# MainBord.net
KiCad netlist of a schematic drawn in Altium Designer
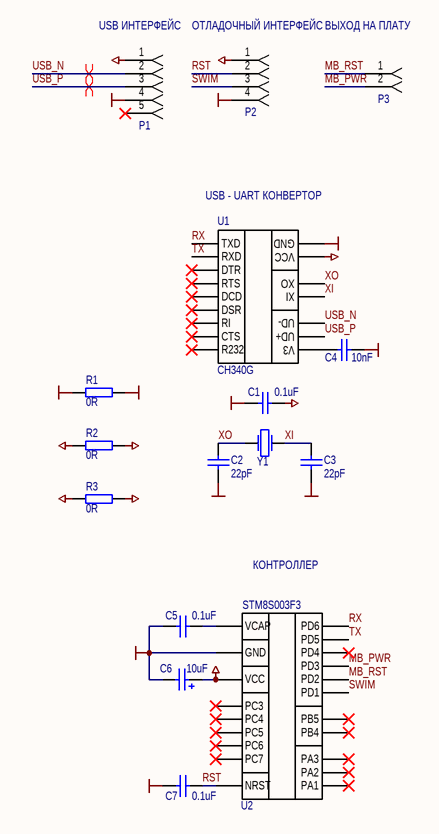
[diagram p0: MainBord.SchDoc]

(export (version "E")
  (design (tool "Eeschema 10.0.6"))
  (components
    (comp (ref "C1")
      (value "0.1uF")
      (footprint "Passive:CAP0603")
      (description "Surface mount ceramic capacitor")
      (fields (field (name "Comment") "CeramicCapacitor"))
      (libsource (lib "Passive") (part "CeramicCapacitor"))
    )
    (comp (ref "C2")
      (value "22pF")
      (footprint "Passive:CAP0402")
      (description "Surface mount ceramic capacitor")
      (fields (field (name "Comment") "CeramicCapacitor"))
      (libsource (lib "Passive") (part "CeramicCapacitor"))
    )
    (comp (ref "C3")
      (value "22pF")
      (footprint "Passive:CAP0402")
      (description "Surface mount ceramic capacitor")
      (fields (field (name "Comment") "CeramicCapacitor"))
      (libsource (lib "Passive") (part "CeramicCapacitor"))
    )
    (comp (ref "C4")
      (value "10nF")
      (footprint "Passive:CAP0603")
      (description "Surface mount ceramic capacitor")
      (fields (field (name "Comment") "CeramicCapacitor"))
      (libsource (lib "Passive") (part "CeramicCapacitor"))
    )
    (comp (ref "C5")
      (value "0.1uF")
      (footprint "Passive:CAP0603")
      (description "Surface mount ceramic capacitor")
      (fields (field (name "Comment") "CeramicCapacitor"))
      (libsource (lib "Passive") (part "CeramicCapacitor"))
    )
    (comp (ref "C6")
      (value "10uF")
      (footprint "Passive:CAP3216")
      (description "Surface mount tantalum capacitor")
      (fields (field (name "Comment") "TantalumCapacitor"))
      (libsource (lib "Passive") (part "TantalumCapacitor"))
    )
    (comp (ref "C7")
      (value "0.1uF")
      (footprint "Passive:CAP0603")
      (description "Surface mount ceramic capacitor")
      (fields (field (name "Comment") "CeramicCapacitor"))
      (libsource (lib "Passive") (part "CeramicCapacitor"))
    )
    (comp (ref "P1")
      (value "Disp")
      (footprint "Connectors:THT_MALE_1x5")
      (libsource (lib "Connectors") (part "XH2.54_5PIN"))
    )
    (comp (ref "P2")
      (value "Disp")
      (footprint "Connectors:653004114822")
      (libsource (lib "Connectors") (part "JST_XH_4PIN"))
    )
    (comp (ref "P3")
      (value "Disp")
      (footprint "Connectors:THT_MALE_1x2")
      (libsource (lib "Connectors") (part "XH2.54_2PIN"))
    )
    (comp (ref "R1")
      (value "0R")
      (footprint "Passive:RES0805_0_Ohm")
      (description "Surface mount resistor")
      (fields (field (name "Comment") "Resistor"))
      (libsource (lib "Passive") (part "Resistor"))
    )
    (comp (ref "R2")
      (value "0R")
      (footprint "Passive:RES0805_0_Ohm")
      (description "Surface mount resistor")
      (fields (field (name "Comment") "Resistor"))
      (libsource (lib "Passive") (part "Resistor"))
    )
    (comp (ref "R3")
      (value "0R")
      (footprint "Passive:RES0805_0_Ohm")
      (description "Surface mount resistor")
      (fields (field (name "Comment") "Resistor"))
      (libsource (lib "Passive") (part "Resistor"))
    )
    (comp (ref "U1")
      (value "CH340G")
      (footprint "IC:SOIC16_CH340G")
      (description "USB to UART Interface")
      (libsource (lib "IC") (part "CH340G"))
    )
    (comp (ref "U2")
      (value "STM8S003F3")
      (footprint "IC:TSOP65P640X120-20N")
      (libsource (lib "IC") (part "STM8S003F3"))
    )
    (comp (ref "Y1")
      (value "XTAL")
      (footprint "Misc:SMD3225")
      (description "Crystal Oscillator")
      (libsource (lib "Misc") (part "XTAL"))
    )
  )
  (nets
    (net (code "1") (name "/MB_PWR") (class "Default")
      (node (ref "P3") (pin "2") (pintype "passive"))
      (node (ref "U2") (pin "20") (pinfunction "PD3_20") (pintype "passive"))
    )
    (net (code "2") (name "/MB_RST") (class "Default")
      (node (ref "P3") (pin "1") (pintype "passive"))
      (node (ref "U2") (pin "19") (pinfunction "PD2_19") (pintype "passive"))
    )
    (net (code "3") (name "/RST") (class "Default")
      (node (ref "C7") (pin "2") (pinfunction "2_2") (pintype "passive"))
      (node (ref "P2") (pin "2") (pintype "passive"))
      (node (ref "U2") (pin "4") (pinfunction "NRST_4") (pintype "passive"))
    )
    (net (code "4") (name "/RX") (class "Default")
      (node (ref "U1") (pin "2") (pinfunction "TXD_2") (pintype "passive"))
      (node (ref "U2") (pin "3") (pinfunction "PD6_3") (pintype "passive"))
    )
    (net (code "5") (name "/SWIM") (class "Default")
      (node (ref "P2") (pin "3") (pintype "passive"))
      (node (ref "U2") (pin "18") (pinfunction "PD1_18") (pintype "passive"))
    )
    (net (code "6") (name "/TX") (class "Default")
      (node (ref "U1") (pin "3") (pinfunction "RXD_3") (pintype "passive"))
      (node (ref "U2") (pin "2") (pinfunction "PD5_2") (pintype "passive"))
    )
    (net (code "7") (name "/USB_N") (class "Default")
      (node (ref "P1") (pin "2") (pintype "passive"))
      (node (ref "U1") (pin "6") (pinfunction "UD-_6") (pintype "passive"))
    )
    (net (code "8") (name "/USB_P") (class "Default")
      (node (ref "P1") (pin "3") (pintype "passive"))
      (node (ref "U1") (pin "5") (pinfunction "UD+_5") (pintype "passive"))
    )
    (net (code "9") (name "/XI") (class "Default")
      (node (ref "C3") (pin "2") (pinfunction "2_2") (pintype "passive"))
      (node (ref "U1") (pin "7") (pinfunction "XI_7") (pintype "passive"))
      (node (ref "Y1") (pin "3") (pinfunction "Out_3") (pintype "passive"))
    )
    (net (code "10") (name "/XO") (class "Default")
      (node (ref "C2") (pin "2") (pinfunction "2_2") (pintype "passive"))
      (node (ref "U1") (pin "8") (pinfunction "XO_8") (pintype "passive"))
      (node (ref "Y1") (pin "1") (pinfunction "In_1") (pintype "passive"))
    )
    (net (code "11") (name "GND") (class "Default")
      (node (ref "C1") (pin "1") (pinfunction "1_1") (pintype "passive"))
      (node (ref "C2") (pin "1") (pinfunction "1_1") (pintype "passive"))
      (node (ref "C3") (pin "1") (pinfunction "1_1") (pintype "passive"))
      (node (ref "C4") (pin "1") (pinfunction "1_1") (pintype "passive"))
      (node (ref "C5") (pin "1") (pinfunction "1_1") (pintype "passive"))
      (node (ref "C6") (pin "1") (pinfunction "1_1") (pintype "passive"))
      (node (ref "C7") (pin "1") (pinfunction "1_1") (pintype "passive"))
      (node (ref "P1") (pin "4") (pintype "passive"))
      (node (ref "P2") (pin "4") (pintype "passive"))
      (node (ref "R1") (pin "1") (pinfunction "1_1") (pintype "passive"))
      (node (ref "R1") (pin "2") (pinfunction "2_2") (pintype "passive"))
      (node (ref "U1") (pin "1") (pinfunction "GND_1") (pintype "passive"))
      (node (ref "U2") (pin "7") (pinfunction "GND_7") (pintype "power_in"))
    )
    (net (code "12") (name "Net-(U1-V3)") (class "Default")
      (node (ref "C4") (pin "2") (pinfunction "2_2") (pintype "passive"))
      (node (ref "U1") (pin "4") (pinfunction "V3_4") (pintype "passive"))
    )
    (net (code "13") (name "Net-(U2-VCAP)") (class "Default")
      (node (ref "C5") (pin "2") (pinfunction "2_2") (pintype "passive"))
      (node (ref "U2") (pin "8") (pinfunction "VCAP_8") (pintype "power_in"))
    )
    (net (code "14") (name "VCC") (class "Default")
      (node (ref "C1") (pin "2") (pinfunction "2_2") (pintype "passive"))
      (node (ref "C6") (pin "2") (pinfunction "2_2") (pintype "passive"))
      (node (ref "P1") (pin "1") (pintype "passive"))
      (node (ref "P2") (pin "1") (pintype "passive"))
      (node (ref "R2") (pin "1") (pinfunction "1_1") (pintype "passive"))
      (node (ref "R2") (pin "2") (pinfunction "2_2") (pintype "passive"))
      (node (ref "R3") (pin "1") (pinfunction "1_1") (pintype "passive"))
      (node (ref "R3") (pin "2") (pinfunction "2_2") (pintype "passive"))
      (node (ref "U1") (pin "16") (pinfunction "VCC_16") (pintype "passive"))
      (node (ref "U2") (pin "9") (pinfunction "VCC_9") (pintype "power_in"))
    )
    (net (code "15") (name "unconnected-(P1-Pad5)") (class "Default")
      (node (ref "P1") (pin "5") (pintype "passive+no_connect"))
    )
    (net (code "16") (name "unconnected-(U1-R232-Pad15)") (class "Default")
      (node (ref "U1") (pin "15") (pinfunction "R232_15") (pintype "passive+no_connect"))
    )
    (net (code "17") (name "unconnected-(U1-~{CTS}-Pad9)") (class "Default")
      (node (ref "U1") (pin "9") (pinfunction "~{CTS}_9") (pintype "passive+no_connect"))
    )
    (net (code "18") (name "unconnected-(U1-~{DCD}-Pad12)") (class "Default")
      (node (ref "U1") (pin "12") (pinfunction "~{DCD}_12") (pintype "passive+no_connect"))
    )
    (net (code "19") (name "unconnected-(U1-~{DSR}-Pad10)") (class "Default")
      (node (ref "U1") (pin "10") (pinfunction "~{DSR}_10") (pintype "passive+no_connect"))
    )
    (net (code "20") (name "unconnected-(U1-~{DTR}-Pad13)") (class "Default")
      (node (ref "U1") (pin "13") (pinfunction "~{DTR}_13") (pintype "passive+no_connect"))
    )
    (net (code "21") (name "unconnected-(U1-~{RI}-Pad11)") (class "Default")
      (node (ref "U1") (pin "11") (pinfunction "~{RI}_11") (pintype "passive+no_connect"))
    )
    (net (code "22") (name "unconnected-(U1-~{RTS}-Pad14)") (class "Default")
      (node (ref "U1") (pin "14") (pinfunction "~{RTS}_14") (pintype "passive+no_connect"))
    )
    (net (code "23") (name "unconnected-(U2-PA1-Pad5)") (class "Default")
      (node (ref "U2") (pin "5") (pinfunction "PA1_5") (pintype "passive+no_connect"))
    )
    (net (code "24") (name "unconnected-(U2-PA2-Pad6)") (class "Default")
      (node (ref "U2") (pin "6") (pinfunction "PA2_6") (pintype "passive+no_connect"))
    )
    (net (code "25") (name "unconnected-(U2-PA3-Pad10)") (class "Default")
      (node (ref "U2") (pin "10") (pinfunction "PA3_10") (pintype "passive+no_connect"))
    )
    (net (code "26") (name "unconnected-(U2-PB4-Pad12)") (class "Default")
      (node (ref "U2") (pin "12") (pinfunction "PB4_12") (pintype "passive+no_connect"))
    )
    (net (code "27") (name "unconnected-(U2-PB5-Pad11)") (class "Default")
      (node (ref "U2") (pin "11") (pinfunction "PB5_11") (pintype "passive+no_connect"))
    )
    (net (code "28") (name "unconnected-(U2-PC3-Pad13)") (class "Default")
      (node (ref "U2") (pin "13") (pinfunction "PC3_13") (pintype "passive+no_connect"))
    )
    (net (code "29") (name "unconnected-(U2-PC4-Pad14)") (class "Default")
      (node (ref "U2") (pin "14") (pinfunction "PC4_14") (pintype "passive+no_connect"))
    )
    (net (code "30") (name "unconnected-(U2-PC5-Pad15)") (class "Default")
      (node (ref "U2") (pin "15") (pinfunction "PC5_15") (pintype "passive+no_connect"))
    )
    (net (code "31") (name "unconnected-(U2-PC6-Pad16)") (class "Default")
      (node (ref "U2") (pin "16") (pinfunction "PC6_16") (pintype "passive+no_connect"))
    )
    (net (code "32") (name "unconnected-(U2-PC7-Pad17)") (class "Default")
      (node (ref "U2") (pin "17") (pinfunction "PC7_17") (pintype "passive+no_connect"))
    )
    (net (code "33") (name "unconnected-(U2-PD4-Pad1)") (class "Default")
      (node (ref "U2") (pin "1") (pinfunction "PD4_1") (pintype "passive+no_connect"))
    )
  )
)
